# 2_Led_Driver.net
KiCad netlist of a schematic drawn in Altium Designer
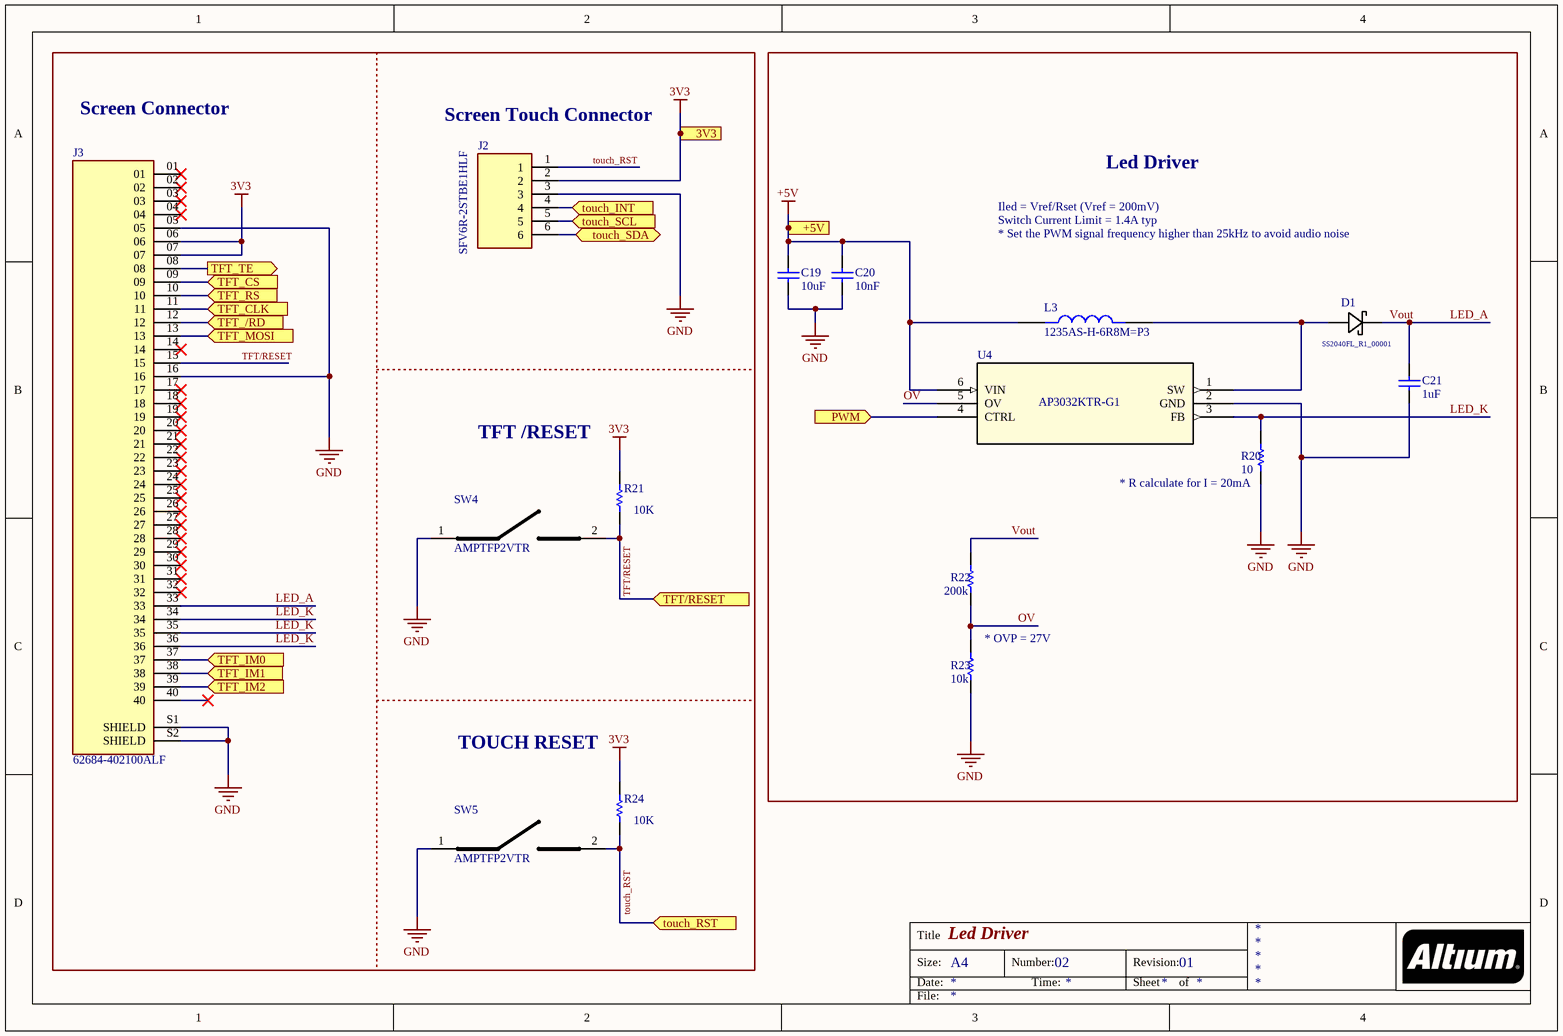
[diagram p0: [2] Led_Driver.SchDoc]

(export (version "E")
  (design (tool "Eeschema 10.0.6"))
  (components
    (comp (ref "C19")
      (value "10uF")
      (footprint "Capacitor 0402")
      (description "Capacitor Ceramico SMD 0402")
      (libsource (lib "Mi Libreria") (part "Capacitor 0402"))
    )
    (comp (ref "C20")
      (value "10nF")
      (footprint "Capacitor 0402")
      (description "Capacitor Ceramico SMD 0402")
      (libsource (lib "Mi Libreria") (part "Capacitor 0402"))
    )
    (comp (ref "C21")
      (value "1uF")
      (footprint "Capacitor 0402")
      (description "Capacitor Ceramico SMD 0402")
      (libsource (lib "Mi Libreria") (part "Capacitor 0402"))
    )
    (comp (ref "D1")
      (value "SS2040FL_R1_00001")
      (footprint "CR_R1_00001_PNJ")
      (description "Description")
      (fields (field (name "COPYRIGHT") "Copyright (C) 2026 Ultra Librarian. All rights reserved."))
      (libsource (lib "SS2040FL_R1_00001") (part "SS2040FL_R1_00001"))
    )
    (comp (ref "J2")
      (value "SFV6R-2STBE1HLF")
      (footprint "AMPHENOL_SFV6R-2STBE1HLF")
      (libsource (lib "SFV6R-2STBE1HLF") (part "SFV6R-2STBE1HLF"))
    )
    (comp (ref "J3")
      (value "62684-402100ALF")
      (footprint "AMPHENOL_62684-402100ALF")
      (fields (field (name "MF") "Amphenol ICC"))
      (libsource (lib "62684-402100ALF") (part "62684-402100ALF"))
    )
    (comp (ref "L3")
      (value "1235AS-H-6R8M=P3")
      (footprint "IND_1235AS-H-6R8M=P3")
      (description "Inductor with Inductance: 6.8uH Tol. +/-20%, Package: 1818 (4745)")
      (fields (field (name "MF") "Murata") (field (name "DIGI-KEY_PART_NUMBER") "490-14206-1-ND"))
      (libsource (lib "1235AS-H-6R8M_P3") (part "1235AS-H-6R8M=P3"))
    )
    (comp (ref "R20")
      (value "10")
      (footprint "Resistencia 0402")
      (description "Resistencia SMD 0402")
      (libsource (lib "Mi Libreria") (part "Resistencia SMD 0402"))
    )
    (comp (ref "R21")
      (value "10K")
      (footprint "Resistencia 0402")
      (description "Resistencia SMD 0402")
      (libsource (lib "Mi Libreria") (part "Resistencia SMD 0402"))
    )
    (comp (ref "R22")
      (value "200k")
      (footprint "Resistencia 0402")
      (description "Resistencia SMD 0402")
      (libsource (lib "Mi Libreria") (part "Resistencia SMD 0402"))
    )
    (comp (ref "R23")
      (value "10k")
      (footprint "Resistencia 0402")
      (description "Resistencia SMD 0402")
      (libsource (lib "Mi Libreria") (part "Resistencia SMD 0402"))
    )
    (comp (ref "R24")
      (value "10K")
      (footprint "Resistencia 0402")
      (description "Resistencia SMD 0402")
      (libsource (lib "Mi Libreria") (part "Resistencia SMD 0402"))
    )
    (comp (ref "SW4")
      (value "AMPTFP2VTR")
      (footprint "AMPTFP2VTR")
      (description "Tactile Switch SPST-NO Top Actuated Surface Mount")
      (fields (field (name "MOUSER PART NUMBER") "642-AMPTFP2VTR"))
      (libsource (lib "AMPTFP2VTR") (part "AMPTFP2VTR"))
    )
    (comp (ref "SW5")
      (value "AMPTFP2VTR")
      (footprint "AMPTFP2VTR")
      (description "Tactile Switch SPST-NO Top Actuated Surface Mount")
      (fields (field (name "MOUSER PART NUMBER") "642-AMPTFP2VTR"))
      (libsource (lib "AMPTFP2VTR") (part "AMPTFP2VTR"))
    )
    (comp (ref "U4")
      (value "AP3032KTR-G1")
      (footprint "SOT23-6_DIO")
      (description "Description")
      (fields (field (name "COPYRIGHT") "Copyright (C) 2025 Ultra Librarian. All rights reserved."))
      (libsource (lib "AP3032KTR-G1") (part "AP3032KTR-G1"))
    )
  )
  (nets
    (net (code "1") (name "+5V") (class "Default")
      (node (ref "C19") (pin "2") (pinfunction "2_2") (pintype "passive"))
      (node (ref "C20") (pin "2") (pinfunction "2_2") (pintype "passive"))
      (node (ref "L3") (pin "1") (pinfunction "1_1") (pintype "passive"))
      (node (ref "U4") (pin "6") (pinfunction "VIN_6") (pintype "input"))
    )
    (net (code "2") (name "/LED_A") (class "Default")
      (node (ref "C21") (pin "2") (pinfunction "2_2") (pintype "passive"))
      (node (ref "D1") (pin "1") (pinfunction "1_1") (pintype "passive"))
      (node (ref "J3") (pin "33") (pinfunction "33_33") (pintype "passive"))
      (node (ref "R22") (pin "2") (pinfunction "B_2") (pintype "passive"))
    )
    (net (code "3") (name "/LED_K") (class "Default")
      (node (ref "J3") (pin "34") (pinfunction "34_34") (pintype "passive"))
      (node (ref "J3") (pin "35") (pinfunction "35_35") (pintype "passive"))
      (node (ref "J3") (pin "36") (pinfunction "36_36") (pintype "passive"))
      (node (ref "R20") (pin "2") (pinfunction "B_2") (pintype "passive"))
      (node (ref "U4") (pin "3") (pinfunction "FB_3") (pintype "output"))
    )
    (net (code "4") (name "/OV") (class "Default")
      (node (ref "R22") (pin "1") (pinfunction "A_1") (pintype "passive"))
      (node (ref "R23") (pin "2") (pinfunction "B_2") (pintype "passive"))
      (node (ref "U4") (pin "5") (pinfunction "OV_5") (pintype "passive"))
    )
    (net (code "5") (name "/PWM") (class "Default")
      (node (ref "U4") (pin "4") (pinfunction "CTRL_4") (pintype "passive"))
    )
    (net (code "6") (name "/TFT_CLK") (class "Default")
      (node (ref "J3") (pin "11") (pinfunction "11_11") (pintype "passive"))
    )
    (net (code "7") (name "/TFT_CS") (class "Default")
      (node (ref "J3") (pin "09") (pinfunction "09_09") (pintype "passive"))
    )
    (net (code "8") (name "/TFT_IM0") (class "Default")
      (node (ref "J3") (pin "37") (pinfunction "37_37") (pintype "passive"))
    )
    (net (code "9") (name "/TFT_IM1") (class "Default")
      (node (ref "J3") (pin "38") (pinfunction "38_38") (pintype "passive"))
    )
    (net (code "10") (name "/TFT_IM2") (class "Default")
      (node (ref "J3") (pin "39") (pinfunction "39_39") (pintype "passive"))
    )
    (net (code "11") (name "/TFT_MOSI") (class "Default")
      (node (ref "J3") (pin "13") (pinfunction "13_13") (pintype "passive"))
    )
    (net (code "12") (name "/TFT_RS") (class "Default")
      (node (ref "J3") (pin "10") (pinfunction "10_10") (pintype "passive"))
    )
    (net (code "13") (name "/TFT_TE") (class "Default")
      (node (ref "J3") (pin "08") (pinfunction "08_08") (pintype "passive"))
    )
    (net (code "14") (name "/TFT_{slash}RD") (class "Default")
      (node (ref "J3") (pin "12") (pinfunction "12_12") (pintype "passive"))
    )
    (net (code "15") (name "/TFT{slash}RESET") (class "Default")
      (node (ref "J3") (pin "15") (pinfunction "15_15") (pintype "passive"))
      (node (ref "R21") (pin "1") (pinfunction "A_1") (pintype "passive"))
      (node (ref "SW4") (pin "2") (pinfunction "NO_2") (pintype "passive"))
    )
    (net (code "16") (name "/touch_INT") (class "Default")
      (node (ref "J2") (pin "4") (pinfunction "4_4") (pintype "passive"))
    )
    (net (code "17") (name "/touch_RST") (class "Default")
      (node (ref "J2") (pin "1") (pinfunction "1_1") (pintype "passive"))
      (node (ref "R24") (pin "1") (pinfunction "A_1") (pintype "passive"))
      (node (ref "SW5") (pin "2") (pinfunction "NO_2") (pintype "passive"))
    )
    (net (code "18") (name "/touch_SCL") (class "Default")
      (node (ref "J2") (pin "5") (pinfunction "5_5") (pintype "passive"))
    )
    (net (code "19") (name "/touch_SDA") (class "Default")
      (node (ref "J2") (pin "6") (pinfunction "6_6") (pintype "passive"))
    )
    (net (code "20") (name "3V3") (class "Default")
      (node (ref "J2") (pin "2") (pinfunction "2_2") (pintype "passive"))
      (node (ref "J3") (pin "06") (pinfunction "06_06") (pintype "passive"))
      (node (ref "J3") (pin "07") (pinfunction "07_07") (pintype "passive"))
      (node (ref "R21") (pin "2") (pinfunction "B_2") (pintype "passive"))
      (node (ref "R24") (pin "2") (pinfunction "B_2") (pintype "passive"))
    )
    (net (code "21") (name "GND") (class "Default")
      (node (ref "C19") (pin "1") (pinfunction "1_1") (pintype "passive"))
      (node (ref "C20") (pin "1") (pinfunction "1_1") (pintype "passive"))
      (node (ref "C21") (pin "1") (pinfunction "1_1") (pintype "passive"))
      (node (ref "J2") (pin "3") (pinfunction "3_3") (pintype "passive"))
      (node (ref "J3") (pin "05") (pinfunction "05_05") (pintype "passive"))
      (node (ref "J3") (pin "16") (pinfunction "16_16") (pintype "passive"))
      (node (ref "J3") (pin "S1") (pinfunction "SHIELD_S1") (pintype "passive"))
      (node (ref "J3") (pin "S2") (pinfunction "SHIELD_S2") (pintype "passive"))
      (node (ref "R20") (pin "1") (pinfunction "A_1") (pintype "passive"))
      (node (ref "R23") (pin "1") (pinfunction "A_1") (pintype "passive"))
      (node (ref "SW4") (pin "1") (pinfunction "COM_1") (pintype "passive"))
      (node (ref "SW5") (pin "1") (pinfunction "COM_1") (pintype "passive"))
      (node (ref "U4") (pin "2") (pinfunction "GND_2") (pintype "power_in"))
    )
    (net (code "22") (name "Net-(U4-SW)") (class "Default")
      (node (ref "D1") (pin "2") (pinfunction "2_2") (pintype "passive"))
      (node (ref "L3") (pin "2") (pinfunction "2_2") (pintype "passive"))
      (node (ref "U4") (pin "1") (pinfunction "SW_1") (pintype "output"))
    )
    (net (code "23") (name "unconnected-(J3-Pad01)") (class "Default")
      (node (ref "J3") (pin "01") (pinfunction "01_01") (pintype "passive+no_connect"))
    )
    (net (code "24") (name "unconnected-(J3-Pad02)") (class "Default")
      (node (ref "J3") (pin "02") (pinfunction "02_02") (pintype "passive+no_connect"))
    )
    (net (code "25") (name "unconnected-(J3-Pad03)") (class "Default")
      (node (ref "J3") (pin "03") (pinfunction "03_03") (pintype "passive+no_connect"))
    )
    (net (code "26") (name "unconnected-(J3-Pad04)") (class "Default")
      (node (ref "J3") (pin "04") (pinfunction "04_04") (pintype "passive+no_connect"))
    )
    (net (code "27") (name "unconnected-(J3-Pad14)") (class "Default")
      (node (ref "J3") (pin "14") (pinfunction "14_14") (pintype "passive+no_connect"))
    )
    (net (code "28") (name "unconnected-(J3-Pad17)") (class "Default")
      (node (ref "J3") (pin "17") (pinfunction "17_17") (pintype "passive+no_connect"))
    )
    (net (code "29") (name "unconnected-(J3-Pad18)") (class "Default")
      (node (ref "J3") (pin "18") (pinfunction "18_18") (pintype "passive+no_connect"))
    )
    (net (code "30") (name "unconnected-(J3-Pad19)") (class "Default")
      (node (ref "J3") (pin "19") (pinfunction "19_19") (pintype "passive+no_connect"))
    )
    (net (code "31") (name "unconnected-(J3-Pad20)") (class "Default")
      (node (ref "J3") (pin "20") (pinfunction "20_20") (pintype "passive+no_connect"))
    )
    (net (code "32") (name "unconnected-(J3-Pad21)") (class "Default")
      (node (ref "J3") (pin "21") (pinfunction "21_21") (pintype "passive+no_connect"))
    )
    (net (code "33") (name "unconnected-(J3-Pad22)") (class "Default")
      (node (ref "J3") (pin "22") (pinfunction "22_22") (pintype "passive+no_connect"))
    )
    (net (code "34") (name "unconnected-(J3-Pad23)") (class "Default")
      (node (ref "J3") (pin "23") (pinfunction "23_23") (pintype "passive+no_connect"))
    )
    (net (code "35") (name "unconnected-(J3-Pad24)") (class "Default")
      (node (ref "J3") (pin "24") (pinfunction "24_24") (pintype "passive+no_connect"))
    )
    (net (code "36") (name "unconnected-(J3-Pad25)") (class "Default")
      (node (ref "J3") (pin "25") (pinfunction "25_25") (pintype "passive+no_connect"))
    )
    (net (code "37") (name "unconnected-(J3-Pad26)") (class "Default")
      (node (ref "J3") (pin "26") (pinfunction "26_26") (pintype "passive+no_connect"))
    )
    (net (code "38") (name "unconnected-(J3-Pad27)") (class "Default")
      (node (ref "J3") (pin "27") (pinfunction "27_27") (pintype "passive+no_connect"))
    )
    (net (code "39") (name "unconnected-(J3-Pad28)") (class "Default")
      (node (ref "J3") (pin "28") (pinfunction "28_28") (pintype "passive+no_connect"))
    )
    (net (code "40") (name "unconnected-(J3-Pad29)") (class "Default")
      (node (ref "J3") (pin "29") (pinfunction "29_29") (pintype "passive+no_connect"))
    )
    (net (code "41") (name "unconnected-(J3-Pad30)") (class "Default")
      (node (ref "J3") (pin "30") (pinfunction "30_30") (pintype "passive+no_connect"))
    )
    (net (code "42") (name "unconnected-(J3-Pad31)") (class "Default")
      (node (ref "J3") (pin "31") (pinfunction "31_31") (pintype "passive+no_connect"))
    )
    (net (code "43") (name "unconnected-(J3-Pad32)") (class "Default")
      (node (ref "J3") (pin "32") (pinfunction "32_32") (pintype "passive+no_connect"))
    )
    (net (code "44") (name "unconnected-(J3-Pad40)") (class "Default")
      (node (ref "J3") (pin "40") (pinfunction "40_40") (pintype "passive+no_connect"))
    )
  )
)
